# 6120.net
KiCad netlist of a schematic drawn in EAGLE
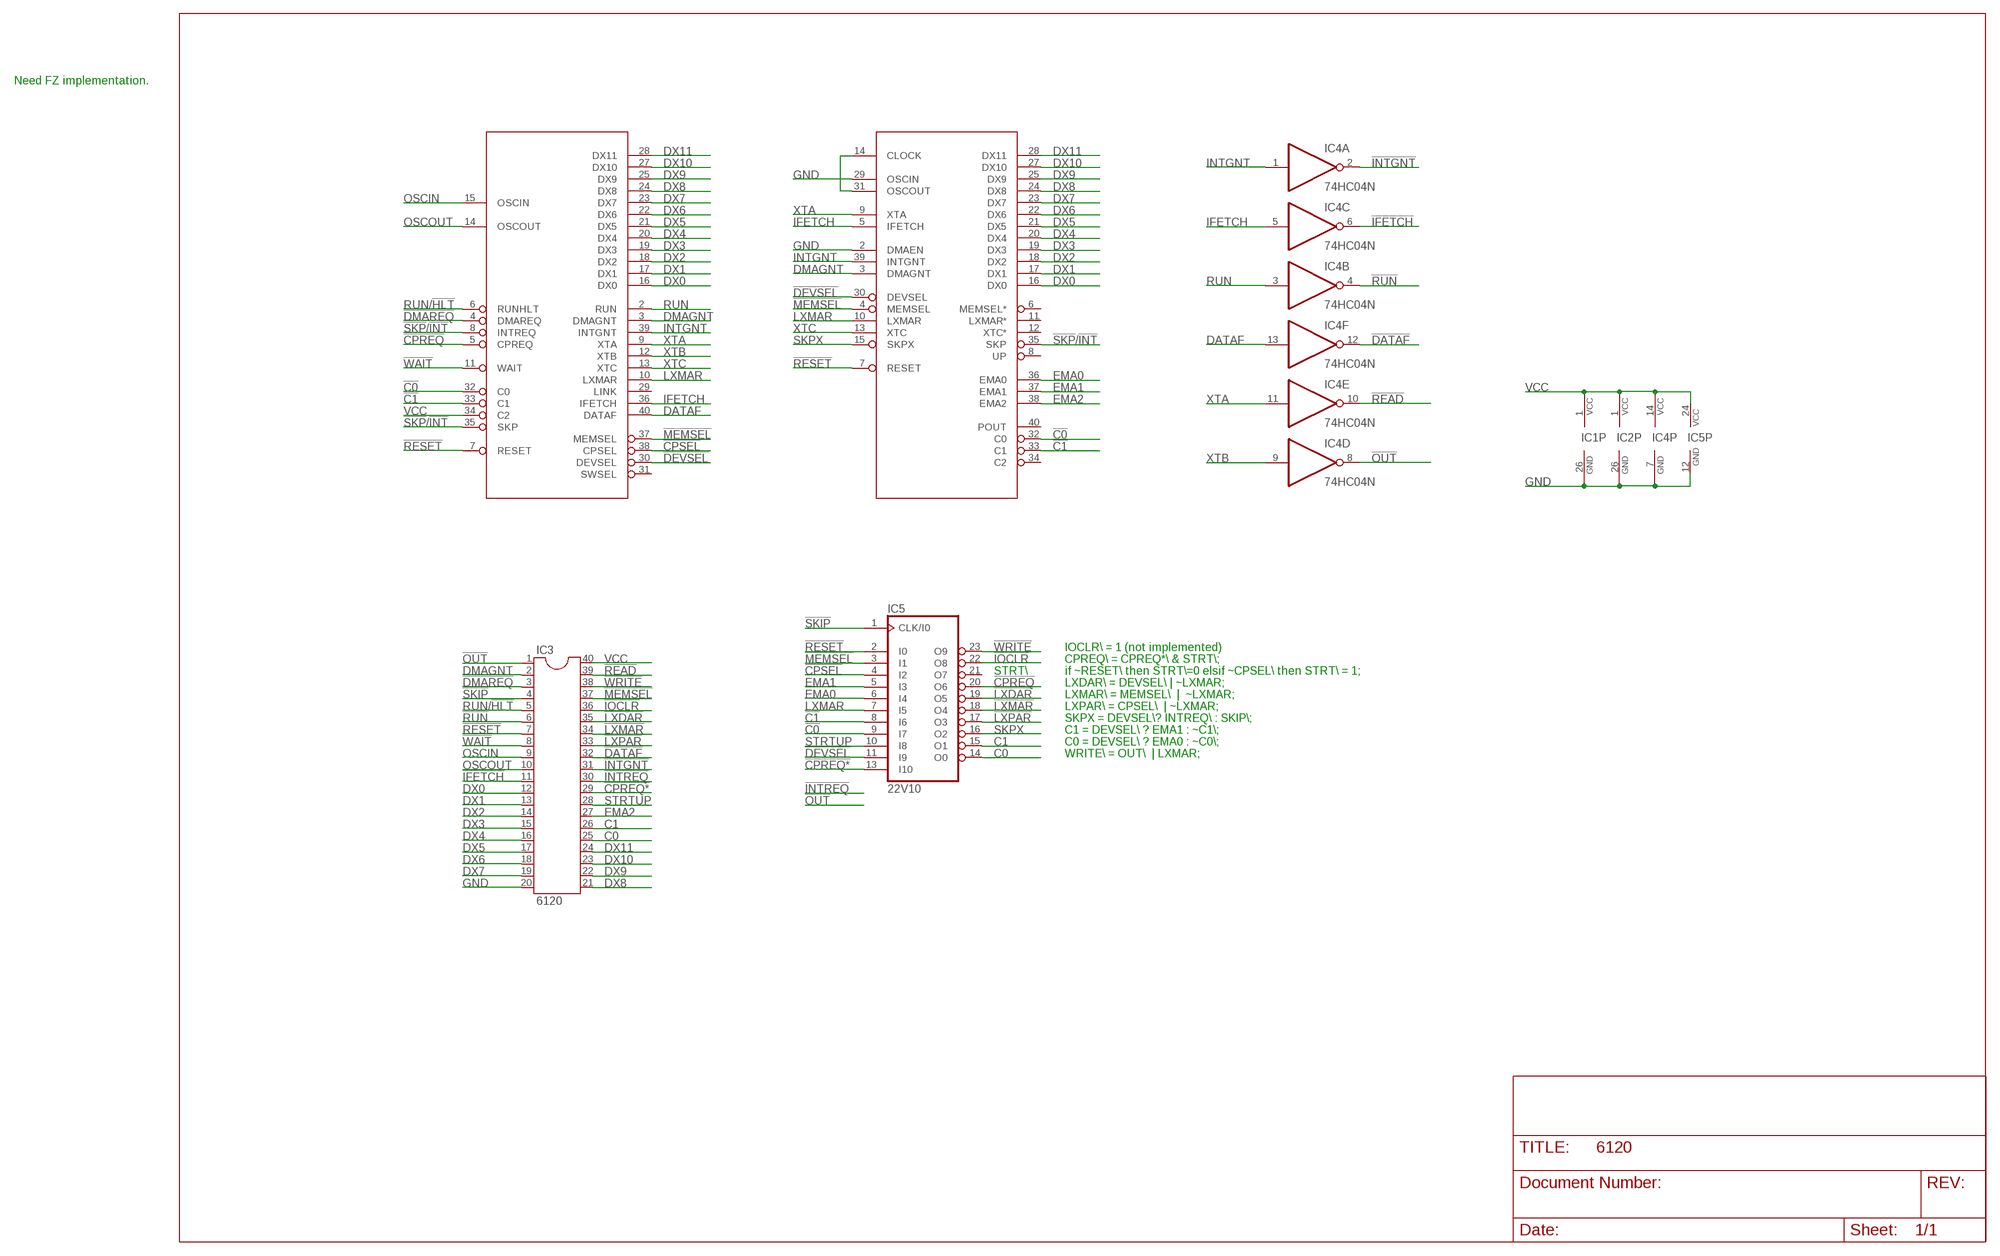
[diagram p0: schematic, sheet 1]

(export (version "E")
  (design (tool "Eeschema 10.0.6"))
  (components
    (comp (ref "IC1")
      (value "IM6100")
      (footprint "eagle-import:DIL40")
      (libsource (lib "eagle-import") (part "IM6100"))
    )
    (comp (ref "IC2")
      (value "IM6102")
      (footprint "eagle-import:DIL40")
      (libsource (lib "eagle-import") (part "IM6102"))
    )
    (comp (ref "IC3")
      (value "6120")
      (footprint "eagle-import:DIL40")
      (libsource (lib "eagle-import") (part "DIL40"))
    )
    (comp (ref "IC4")
      (value "74HC04N")
      (footprint "eagle-import:DIL14")
      (libsource (lib "eagle-import") (part "7404NS"))
    )
    (comp (ref "IC5")
      (value "22V10")
      (footprint "eagle-import:DIL24-3")
      (fields (field (name "MPN") "GAL22V10D-7LPN"))
      (libsource (lib "eagle-import") (part "22V10"))
    )
  )
  (nets
    (net (code "1") (name "/C0") (class "Default")
      (node (ref "IC3") (pin "25") (pinfunction "25_25") (pintype "passive"))
      (node (ref "IC5") (pin "14") (pinfunction "O0_14") (pintype "bidirectional"))
    )
    (net (code "2") (name "/C1") (class "Default")
      (node (ref "IC3") (pin "26") (pinfunction "26_26") (pintype "passive"))
      (node (ref "IC5") (pin "15") (pinfunction "O1_15") (pintype "bidirectional"))
    )
    (net (code "3") (name "/DATAF") (class "Default")
      (node (ref "IC1") (pin "40") (pinfunction "DATAF_40") (pintype "output"))
      (node (ref "IC4") (pin "13") (pinfunction "I_13") (pintype "input"))
    )
    (net (code "4") (name "/DMAGNT") (class "Default")
      (node (ref "IC1") (pin "3") (pinfunction "DMAGNT_3") (pintype "output"))
      (node (ref "IC2") (pin "3") (pinfunction "DMAGNT_3") (pintype "input"))
      (node (ref "IC3") (pin "2") (pinfunction "2_2") (pintype "passive"))
    )
    (net (code "5") (name "/DX0") (class "Default")
      (node (ref "IC1") (pin "16") (pinfunction "DX0_16") (pintype "bidirectional"))
      (node (ref "IC2") (pin "16") (pinfunction "DX0_16") (pintype "bidirectional"))
      (node (ref "IC3") (pin "12") (pinfunction "12_12") (pintype "passive"))
    )
    (net (code "6") (name "/DX1") (class "Default")
      (node (ref "IC1") (pin "17") (pinfunction "DX1_17") (pintype "bidirectional"))
      (node (ref "IC2") (pin "17") (pinfunction "DX1_17") (pintype "bidirectional"))
      (node (ref "IC3") (pin "13") (pinfunction "13_13") (pintype "passive"))
    )
    (net (code "7") (name "/DX2") (class "Default")
      (node (ref "IC1") (pin "18") (pinfunction "DX2_18") (pintype "bidirectional"))
      (node (ref "IC2") (pin "18") (pinfunction "DX2_18") (pintype "bidirectional"))
      (node (ref "IC3") (pin "14") (pinfunction "14_14") (pintype "passive"))
    )
    (net (code "8") (name "/DX3") (class "Default")
      (node (ref "IC1") (pin "19") (pinfunction "DX3_19") (pintype "bidirectional"))
      (node (ref "IC2") (pin "19") (pinfunction "DX3_19") (pintype "bidirectional"))
      (node (ref "IC3") (pin "15") (pinfunction "15_15") (pintype "passive"))
    )
    (net (code "9") (name "/DX4") (class "Default")
      (node (ref "IC1") (pin "20") (pinfunction "DX4_20") (pintype "bidirectional"))
      (node (ref "IC2") (pin "20") (pinfunction "DX4_20") (pintype "bidirectional"))
      (node (ref "IC3") (pin "16") (pinfunction "16_16") (pintype "passive"))
    )
    (net (code "10") (name "/DX5") (class "Default")
      (node (ref "IC1") (pin "21") (pinfunction "DX5_21") (pintype "bidirectional"))
      (node (ref "IC2") (pin "21") (pinfunction "DX5_21") (pintype "bidirectional"))
      (node (ref "IC3") (pin "17") (pinfunction "17_17") (pintype "passive"))
    )
    (net (code "11") (name "/DX6") (class "Default")
      (node (ref "IC1") (pin "22") (pinfunction "DX6_22") (pintype "bidirectional"))
      (node (ref "IC2") (pin "22") (pinfunction "DX6_22") (pintype "bidirectional"))
      (node (ref "IC3") (pin "18") (pinfunction "18_18") (pintype "passive"))
    )
    (net (code "12") (name "/DX7") (class "Default")
      (node (ref "IC1") (pin "23") (pinfunction "DX7_23") (pintype "bidirectional"))
      (node (ref "IC2") (pin "23") (pinfunction "DX7_23") (pintype "bidirectional"))
      (node (ref "IC3") (pin "19") (pinfunction "19_19") (pintype "passive"))
    )
    (net (code "13") (name "/DX8") (class "Default")
      (node (ref "IC1") (pin "24") (pinfunction "DX8_24") (pintype "bidirectional"))
      (node (ref "IC2") (pin "24") (pinfunction "DX8_24") (pintype "bidirectional"))
      (node (ref "IC3") (pin "21") (pinfunction "21_21") (pintype "passive"))
    )
    (net (code "14") (name "/DX9") (class "Default")
      (node (ref "IC1") (pin "25") (pinfunction "DX9_25") (pintype "bidirectional"))
      (node (ref "IC2") (pin "25") (pinfunction "DX9_25") (pintype "bidirectional"))
      (node (ref "IC3") (pin "22") (pinfunction "22_22") (pintype "passive"))
    )
    (net (code "15") (name "/DX10") (class "Default")
      (node (ref "IC1") (pin "27") (pinfunction "DX10_27") (pintype "bidirectional"))
      (node (ref "IC2") (pin "27") (pinfunction "DX10_27") (pintype "bidirectional"))
      (node (ref "IC3") (pin "23") (pinfunction "23_23") (pintype "passive"))
    )
    (net (code "16") (name "/DX11") (class "Default")
      (node (ref "IC1") (pin "28") (pinfunction "DX11_28") (pintype "bidirectional"))
      (node (ref "IC2") (pin "28") (pinfunction "DX11_28") (pintype "bidirectional"))
      (node (ref "IC3") (pin "24") (pinfunction "24_24") (pintype "passive"))
    )
    (net (code "17") (name "/EMA0") (class "Default")
      (node (ref "IC2") (pin "36") (pinfunction "EMA0_36") (pintype "output"))
      (node (ref "IC5") (pin "6") (pinfunction "I4_6") (pintype "input"))
    )
    (net (code "18") (name "/EMA1") (class "Default")
      (node (ref "IC2") (pin "37") (pinfunction "EMA1_37") (pintype "output"))
      (node (ref "IC5") (pin "5") (pinfunction "I3_5") (pintype "input"))
    )
    (net (code "19") (name "/EMA2") (class "Default")
      (node (ref "IC2") (pin "38") (pinfunction "EMA2_38") (pintype "output"))
      (node (ref "IC3") (pin "27") (pinfunction "27_27") (pintype "passive"))
    )
    (net (code "20") (name "/GND") (class "Default")
      (node (ref "IC1") (pin "26") (pinfunction "GND_26") (pintype "power_in"))
      (node (ref "IC2") (pin "2") (pinfunction "DMAEN_2") (pintype "input"))
      (node (ref "IC2") (pin "26") (pinfunction "GND_26") (pintype "power_in"))
      (node (ref "IC2") (pin "29") (pinfunction "OSCIN_29") (pintype "input"))
      (node (ref "IC3") (pin "20") (pinfunction "20_20") (pintype "passive"))
      (node (ref "IC4") (pin "7") (pinfunction "GND_7") (pintype "power_in"))
      (node (ref "IC5") (pin "12") (pinfunction "GND_12") (pintype "power_in"))
    )
    (net (code "21") (name "/IFETCH") (class "Default")
      (node (ref "IC1") (pin "36") (pinfunction "IFETCH_36") (pintype "output"))
      (node (ref "IC2") (pin "5") (pinfunction "IFETCH_5") (pintype "input"))
      (node (ref "IC4") (pin "5") (pinfunction "I_5") (pintype "input"))
    )
    (net (code "22") (name "/INTGNT") (class "Default")
      (node (ref "IC1") (pin "39") (pinfunction "INTGNT_39") (pintype "output"))
      (node (ref "IC2") (pin "39") (pinfunction "INTGNT_39") (pintype "input"))
      (node (ref "IC4") (pin "1") (pinfunction "I_1") (pintype "input"))
    )
    (net (code "23") (name "/LXMAR") (class "Default")
      (node (ref "IC1") (pin "10") (pinfunction "LXMAR_10") (pintype "output"))
      (node (ref "IC2") (pin "10") (pinfunction "LXMAR_10") (pintype "input"))
      (node (ref "IC5") (pin "7") (pinfunction "I5_7") (pintype "input"))
    )
    (net (code "24") (name "/OSCIN") (class "Default")
      (node (ref "IC1") (pin "15") (pinfunction "OSCIN_15") (pintype "input"))
      (node (ref "IC3") (pin "9") (pinfunction "9_9") (pintype "passive"))
    )
    (net (code "25") (name "/OSCOUT") (class "Default")
      (node (ref "IC1") (pin "14") (pinfunction "OSCOUT_14") (pintype "output"))
      (node (ref "IC3") (pin "10") (pinfunction "10_10") (pintype "passive"))
    )
    (net (code "26") (name "/RUN") (class "Default")
      (node (ref "IC1") (pin "2") (pinfunction "RUN_2") (pintype "output"))
      (node (ref "IC4") (pin "3") (pinfunction "I_3") (pintype "input"))
    )
    (net (code "27") (name "/RUN{slash}~{HLT}") (class "Default")
      (node (ref "IC1") (pin "6") (pinfunction "RUNHLT_6") (pintype "input"))
      (node (ref "IC3") (pin "5") (pinfunction "5_5") (pintype "passive"))
    )
    (net (code "28") (name "/SKPX") (class "Default")
      (node (ref "IC2") (pin "15") (pinfunction "SKPX_15") (pintype "input"))
      (node (ref "IC5") (pin "16") (pinfunction "O2_16") (pintype "bidirectional"))
    )
    (net (code "29") (name "/STRTUP") (class "Default")
      (node (ref "IC3") (pin "28") (pinfunction "28_28") (pintype "passive"))
      (node (ref "IC5") (pin "10") (pinfunction "I8_10") (pintype "input"))
    )
    (net (code "30") (name "/VCC") (class "Default")
      (node (ref "IC1") (pin "1") (pinfunction "VCC_1") (pintype "power_in"))
      (node (ref "IC1") (pin "34") (pinfunction "C2_34") (pintype "input"))
      (node (ref "IC2") (pin "1") (pinfunction "VCC_1") (pintype "power_in"))
      (node (ref "IC3") (pin "40") (pinfunction "40_40") (pintype "passive"))
      (node (ref "IC4") (pin "14") (pinfunction "VCC_14") (pintype "power_in"))
      (node (ref "IC5") (pin "24") (pinfunction "VCC_24") (pintype "power_in"))
    )
    (net (code "31") (name "/XTA") (class "Default")
      (node (ref "IC1") (pin "9") (pinfunction "XTA_9") (pintype "output"))
      (node (ref "IC2") (pin "9") (pinfunction "XTA_9") (pintype "input"))
      (node (ref "IC4") (pin "11") (pinfunction "I_11") (pintype "input"))
    )
    (net (code "32") (name "/XTB") (class "Default")
      (node (ref "IC1") (pin "12") (pinfunction "XTB_12") (pintype "output"))
      (node (ref "IC4") (pin "9") (pinfunction "I_9") (pintype "input"))
    )
    (net (code "33") (name "/XTC") (class "Default")
      (node (ref "IC1") (pin "13") (pinfunction "XTC_13") (pintype "output"))
      (node (ref "IC2") (pin "13") (pinfunction "XTC_13") (pintype "input"))
    )
    (net (code "34") (name "/~{C0}") (class "Default")
      (node (ref "IC1") (pin "32") (pinfunction "C0_32") (pintype "input"))
      (node (ref "IC2") (pin "32") (pinfunction "C0_32") (pintype "open_collector"))
      (node (ref "IC5") (pin "9") (pinfunction "I7_9") (pintype "input"))
    )
    (net (code "35") (name "/~{C1}") (class "Default")
      (node (ref "IC1") (pin "33") (pinfunction "C1_33") (pintype "input"))
      (node (ref "IC2") (pin "33") (pinfunction "C1_33") (pintype "open_collector"))
      (node (ref "IC5") (pin "8") (pinfunction "I6_8") (pintype "input"))
    )
    (net (code "36") (name "/~{CPREQ*}") (class "Default")
      (node (ref "IC3") (pin "29") (pinfunction "29_29") (pintype "passive"))
      (node (ref "IC5") (pin "13") (pinfunction "I10_13") (pintype "input"))
    )
    (net (code "37") (name "/~{CPREQ}") (class "Default")
      (node (ref "IC1") (pin "5") (pinfunction "CPREQ_5") (pintype "input"))
      (node (ref "IC5") (pin "20") (pinfunction "O6_20") (pintype "bidirectional"))
    )
    (net (code "38") (name "/~{CPSEL}") (class "Default")
      (node (ref "IC1") (pin "38") (pinfunction "CPSEL_38") (pintype "output"))
      (node (ref "IC5") (pin "4") (pinfunction "I2_4") (pintype "input"))
    )
    (net (code "39") (name "/~{DATAF}") (class "Default")
      (node (ref "IC3") (pin "32") (pinfunction "32_32") (pintype "passive"))
      (node (ref "IC4") (pin "12") (pinfunction "O_12") (pintype "output"))
    )
    (net (code "40") (name "/~{DEVSEL}") (class "Default")
      (node (ref "IC1") (pin "30") (pinfunction "DEVSEL_30") (pintype "output"))
      (node (ref "IC2") (pin "30") (pinfunction "DEVSEL_30") (pintype "input"))
      (node (ref "IC5") (pin "11") (pinfunction "I9_11") (pintype "input"))
    )
    (net (code "41") (name "/~{DMAREQ}") (class "Default")
      (node (ref "IC1") (pin "4") (pinfunction "DMAREQ_4") (pintype "input"))
      (node (ref "IC3") (pin "3") (pinfunction "3_3") (pintype "passive"))
    )
    (net (code "42") (name "/~{IFETCH}") (class "Default")
      (node (ref "IC3") (pin "11") (pinfunction "11_11") (pintype "passive"))
      (node (ref "IC4") (pin "6") (pinfunction "O_6") (pintype "output"))
    )
    (net (code "43") (name "/~{INTGNT}") (class "Default")
      (node (ref "IC3") (pin "31") (pinfunction "31_31") (pintype "passive"))
      (node (ref "IC4") (pin "2") (pinfunction "O_2") (pintype "output"))
    )
    (net (code "44") (name "/~{INTREQ}") (class "Default")
      (node (ref "IC3") (pin "30") (pinfunction "30_30") (pintype "passive"))
    )
    (net (code "45") (name "/~{IOCLR}") (class "Default")
      (node (ref "IC3") (pin "36") (pinfunction "36_36") (pintype "passive"))
      (node (ref "IC5") (pin "22") (pinfunction "O8_22") (pintype "bidirectional"))
    )
    (net (code "46") (name "/~{LXDAR}") (class "Default")
      (node (ref "IC3") (pin "35") (pinfunction "35_35") (pintype "passive"))
      (node (ref "IC5") (pin "19") (pinfunction "O5_19") (pintype "bidirectional"))
    )
    (net (code "47") (name "/~{LXMAR}") (class "Default")
      (node (ref "IC3") (pin "34") (pinfunction "34_34") (pintype "passive"))
      (node (ref "IC5") (pin "18") (pinfunction "O4_18") (pintype "bidirectional"))
    )
    (net (code "48") (name "/~{LXPAR}") (class "Default")
      (node (ref "IC3") (pin "33") (pinfunction "33_33") (pintype "passive"))
      (node (ref "IC5") (pin "17") (pinfunction "O3_17") (pintype "bidirectional"))
    )
    (net (code "49") (name "/~{MEMSEL}") (class "Default")
      (node (ref "IC1") (pin "37") (pinfunction "MEMSEL_37") (pintype "output"))
      (node (ref "IC2") (pin "4") (pinfunction "MEMSEL_4") (pintype "input"))
      (node (ref "IC3") (pin "37") (pinfunction "37_37") (pintype "passive"))
      (node (ref "IC5") (pin "3") (pinfunction "I1_3") (pintype "input"))
    )
    (net (code "50") (name "/~{OUT}") (class "Default")
      (node (ref "IC3") (pin "1") (pinfunction "1_1") (pintype "passive"))
      (node (ref "IC4") (pin "8") (pinfunction "O_8") (pintype "output"))
    )
    (net (code "51") (name "/~{READ}") (class "Default")
      (node (ref "IC3") (pin "39") (pinfunction "39_39") (pintype "passive"))
      (node (ref "IC4") (pin "10") (pinfunction "O_10") (pintype "output"))
    )
    (net (code "52") (name "/~{RESET}") (class "Default")
      (node (ref "IC1") (pin "7") (pinfunction "RESET_7") (pintype "input"))
      (node (ref "IC2") (pin "7") (pinfunction "RESET_7") (pintype "input"))
      (node (ref "IC3") (pin "7") (pinfunction "7_7") (pintype "passive"))
      (node (ref "IC5") (pin "2") (pinfunction "I0_2") (pintype "input"))
    )
    (net (code "53") (name "/~{RUN}") (class "Default")
      (node (ref "IC3") (pin "6") (pinfunction "6_6") (pintype "passive"))
      (node (ref "IC4") (pin "4") (pinfunction "O_4") (pintype "output"))
    )
    (net (code "54") (name "/~{SKIP}") (class "Default")
      (node (ref "IC3") (pin "4") (pinfunction "4_4") (pintype "passive"))
      (node (ref "IC5") (pin "1") (pinfunction "CLK/I0_1") (pintype "input"))
    )
    (net (code "55") (name "/~{SKP}{slash}~{INT}") (class "Default")
      (node (ref "IC1") (pin "35") (pinfunction "SKP_35") (pintype "input"))
      (node (ref "IC1") (pin "8") (pinfunction "INTREQ_8") (pintype "input"))
      (node (ref "IC2") (pin "35") (pinfunction "SKP_35") (pintype "output"))
    )
    (net (code "56") (name "/~{WAIT}") (class "Default")
      (node (ref "IC1") (pin "11") (pinfunction "WAIT_11") (pintype "input"))
      (node (ref "IC3") (pin "8") (pinfunction "8_8") (pintype "passive"))
    )
    (net (code "57") (name "/~{WRITE}") (class "Default")
      (node (ref "IC3") (pin "38") (pinfunction "38_38") (pintype "passive"))
      (node (ref "IC5") (pin "23") (pinfunction "O9_23") (pintype "bidirectional"))
    )
    (net (code "58") (name "Net-(IC2A-CLOCK)") (class "Default")
      (node (ref "IC2") (pin "14") (pinfunction "CLOCK_14") (pintype "input"))
      (node (ref "IC2") (pin "31") (pinfunction "OSCOUT_31") (pintype "output"))
    )
    (net (code "59") (name "unconnected-(IC1A-LINK-Pad29)") (class "Default")
      (node (ref "IC1") (pin "29") (pinfunction "LINK_29") (pintype "output"))
    )
    (net (code "60") (name "unconnected-(IC1A-SWSEL-Pad31)") (class "Default")
      (node (ref "IC1") (pin "31") (pinfunction "SWSEL_31") (pintype "output"))
    )
    (net (code "61") (name "unconnected-(IC2A-C2-Pad34)") (class "Default")
      (node (ref "IC2") (pin "34") (pinfunction "C2_34") (pintype "open_collector"))
    )
    (net (code "62") (name "unconnected-(IC2A-LXMAR*-Pad11)") (class "Default")
      (node (ref "IC2") (pin "11") (pinfunction "LXMAR*_11") (pintype "output"))
    )
    (net (code "63") (name "unconnected-(IC2A-MEMSEL*-Pad6)") (class "Default")
      (node (ref "IC2") (pin "6") (pinfunction "MEMSEL*_6") (pintype "output"))
    )
    (net (code "64") (name "unconnected-(IC2A-POUT-Pad40)") (class "Default")
      (node (ref "IC2") (pin "40") (pinfunction "POUT_40") (pintype "output"))
    )
    (net (code "65") (name "unconnected-(IC2A-UP-Pad8)") (class "Default")
      (node (ref "IC2") (pin "8") (pinfunction "UP_8") (pintype "output"))
    )
    (net (code "66") (name "unconnected-(IC2A-XTC*-Pad12)") (class "Default")
      (node (ref "IC2") (pin "12") (pinfunction "XTC*_12") (pintype "output"))
    )
    (net (code "67") (name "unconnected-(IC5A-O7-Pad21)") (class "Default")
      (node (ref "IC5") (pin "21") (pinfunction "O7_21") (pintype "bidirectional"))
    )
  )
)
